# light_controller.net
KiCad netlist of a schematic drawn in EAGLE
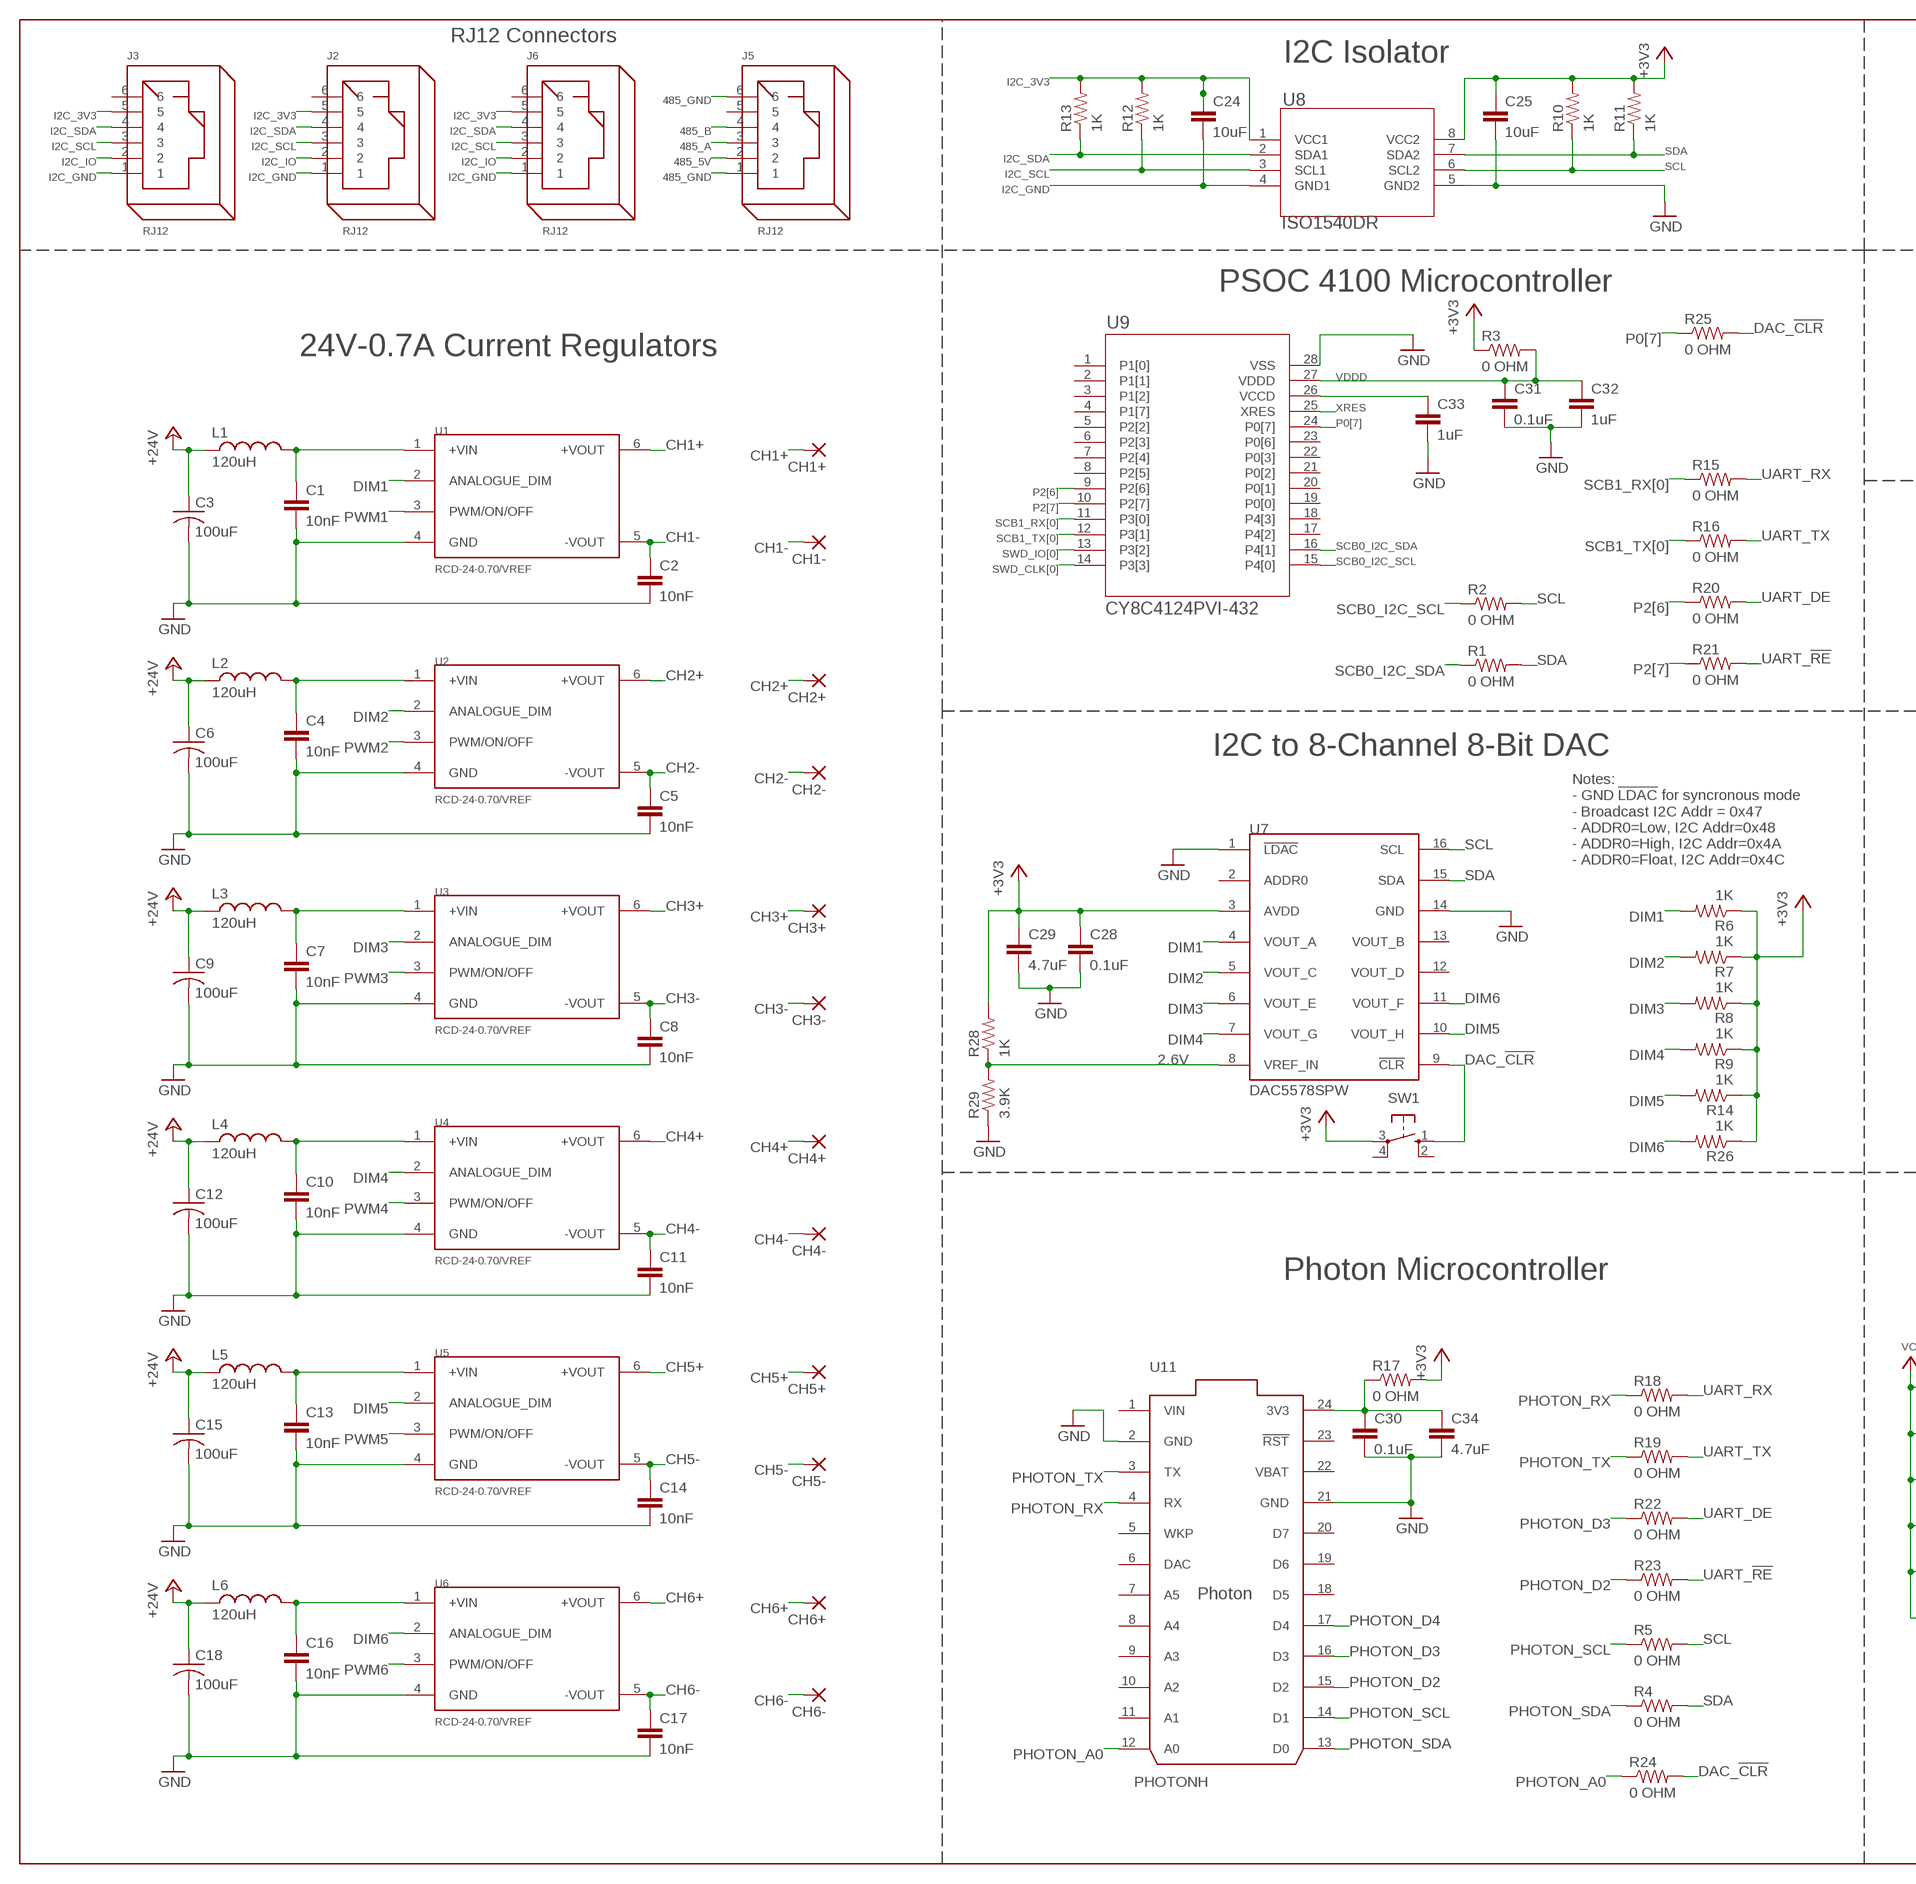
[diagram p0: schematic, sheet 1, part 1 of 2]
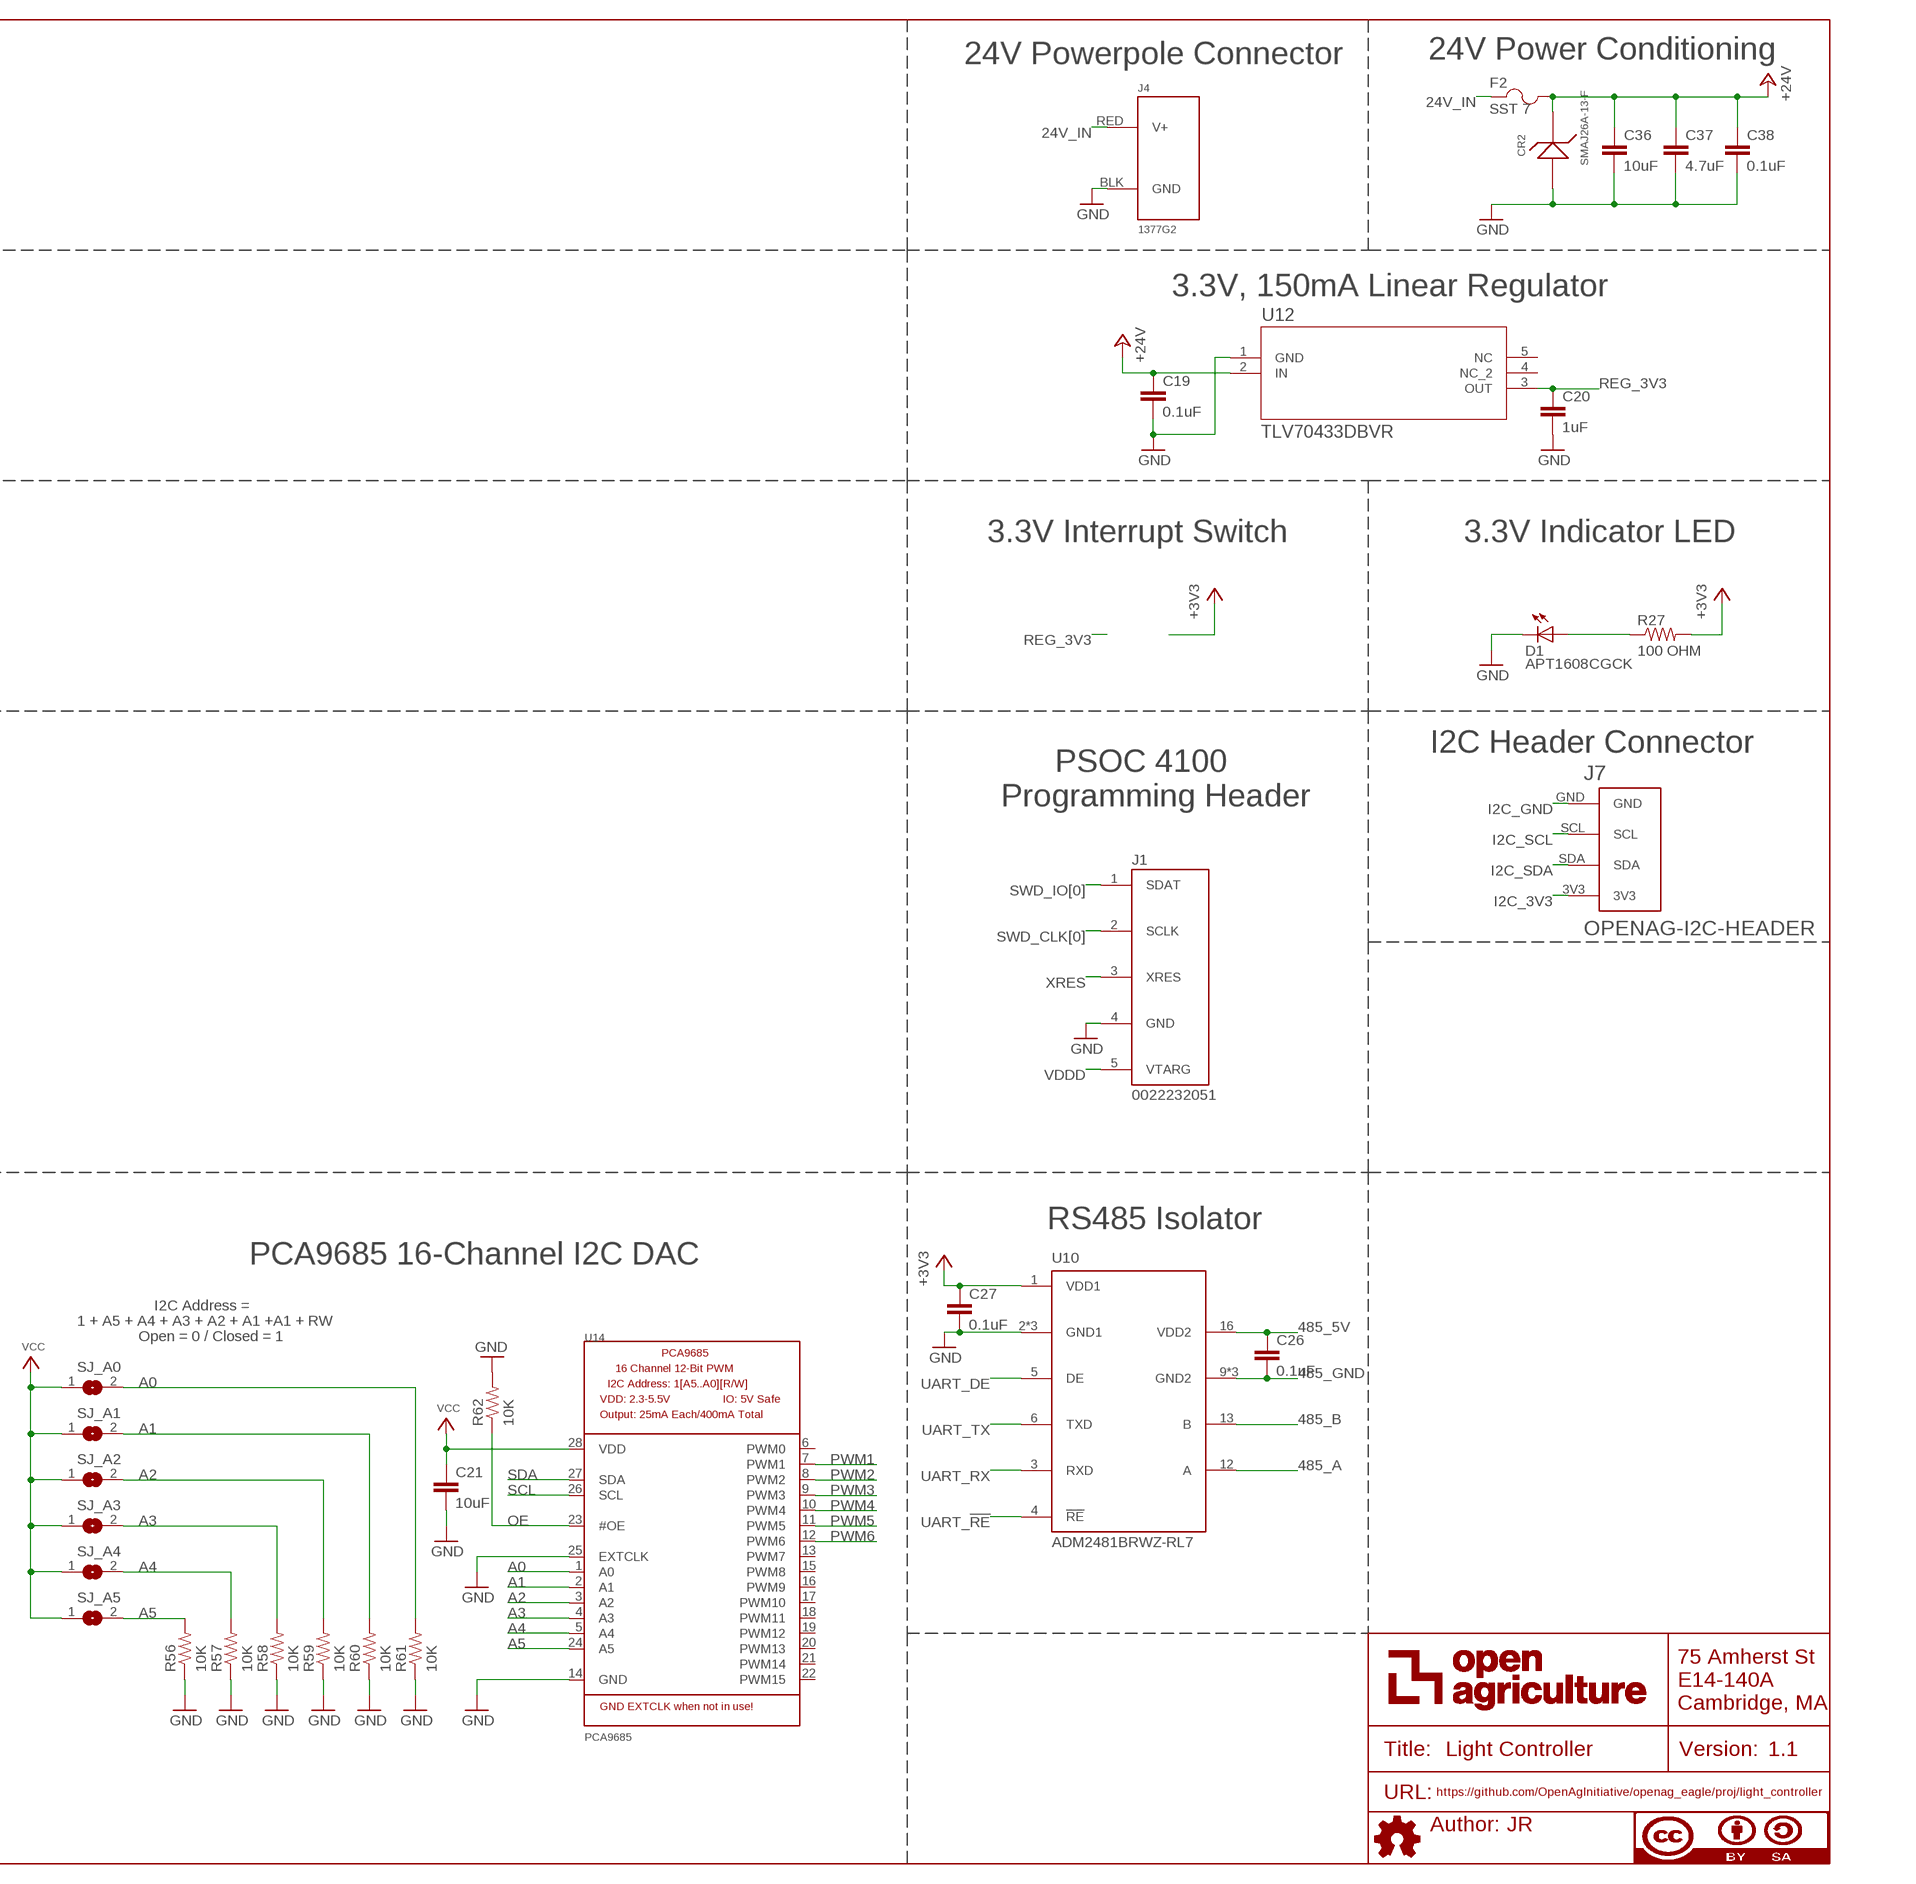
[diagram p1: schematic, sheet 1, part 2 of 2]

(export (version "E")
  (design (tool "Eeschema 10.0.6"))
  (components
    (comp (ref "C1")
      (value "10nF")
      (footprint "eagle-import:C0603")
      (libsource (lib "eagle-import") (part "10NF-C0603C103K5RACTU"))
    )
    (comp (ref "C2")
      (value "10nF")
      (footprint "eagle-import:C0603")
      (libsource (lib "eagle-import") (part "10NF-C0603C103K5RACTU"))
    )
    (comp (ref "C3")
      (value "100uF")
      (footprint "eagle-import:EEE-1HA101UP")
      (libsource (lib "eagle-import") (part "100UF-EEE-1HA101UP"))
    )
    (comp (ref "C4")
      (value "10nF")
      (footprint "eagle-import:C0603")
      (libsource (lib "eagle-import") (part "10NF-C0603C103K5RACTU"))
    )
    (comp (ref "C5")
      (value "10nF")
      (footprint "eagle-import:C0603")
      (libsource (lib "eagle-import") (part "10NF-C0603C103K5RACTU"))
    )
    (comp (ref "C6")
      (value "100uF")
      (footprint "eagle-import:EEE-1HA101UP")
      (libsource (lib "eagle-import") (part "100UF-EEE-1HA101UP"))
    )
    (comp (ref "C7")
      (value "10nF")
      (footprint "eagle-import:C0603")
      (libsource (lib "eagle-import") (part "10NF-C0603C103K5RACTU"))
    )
    (comp (ref "C8")
      (value "10nF")
      (footprint "eagle-import:C0603")
      (libsource (lib "eagle-import") (part "10NF-C0603C103K5RACTU"))
    )
    (comp (ref "C9")
      (value "100uF")
      (footprint "eagle-import:EEE-1HA101UP")
      (libsource (lib "eagle-import") (part "100UF-EEE-1HA101UP"))
    )
    (comp (ref "C10")
      (value "10nF")
      (footprint "eagle-import:C0603")
      (libsource (lib "eagle-import") (part "10NF-C0603C103K5RACTU"))
    )
    (comp (ref "C11")
      (value "10nF")
      (footprint "eagle-import:C0603")
      (libsource (lib "eagle-import") (part "10NF-C0603C103K5RACTU"))
    )
    (comp (ref "C12")
      (value "100uF")
      (footprint "eagle-import:EEE-1HA101UP")
      (libsource (lib "eagle-import") (part "100UF-EEE-1HA101UP"))
    )
    (comp (ref "C13")
      (value "10nF")
      (footprint "eagle-import:C0603")
      (libsource (lib "eagle-import") (part "10NF-C0603C103K5RACTU"))
    )
    (comp (ref "C14")
      (value "10nF")
      (footprint "eagle-import:C0603")
      (libsource (lib "eagle-import") (part "10NF-C0603C103K5RACTU"))
    )
    (comp (ref "C15")
      (value "100uF")
      (footprint "eagle-import:EEE-1HA101UP")
      (libsource (lib "eagle-import") (part "100UF-EEE-1HA101UP"))
    )
    (comp (ref "C16")
      (value "10nF")
      (footprint "eagle-import:C0603")
      (libsource (lib "eagle-import") (part "10NF-C0603C103K5RACTU"))
    )
    (comp (ref "C17")
      (value "10nF")
      (footprint "eagle-import:C0603")
      (libsource (lib "eagle-import") (part "10NF-C0603C103K5RACTU"))
    )
    (comp (ref "C18")
      (value "100uF")
      (footprint "eagle-import:EEE-1HA101UP")
      (libsource (lib "eagle-import") (part "100UF-EEE-1HA101UP"))
    )
    (comp (ref "C19")
      (value "0.1uF")
      (footprint "eagle-import:C0603")
      (libsource (lib "eagle-import") (part "0.1UF-C0603C104K5RACTU"))
    )
    (comp (ref "C20")
      (value "1uF")
      (footprint "eagle-import:C0603")
      (libsource (lib "eagle-import") (part "1UF-CL10A105KB8NNNC"))
    )
    (comp (ref "C21")
      (value "10uF")
      (footprint "eagle-import:C0805")
      (libsource (lib "eagle-import") (part "10UF-GMK212BBJ106KG-T"))
    )
    (comp (ref "C24")
      (value "10uF")
      (footprint "eagle-import:C0805")
      (libsource (lib "eagle-import") (part "10UF-GMK212BBJ106KG-T"))
    )
    (comp (ref "C25")
      (value "10uF")
      (footprint "eagle-import:C0805")
      (libsource (lib "eagle-import") (part "10UF-GMK212BBJ106KG-T"))
    )
    (comp (ref "C26")
      (value "0.1uF")
      (footprint "eagle-import:C0603")
      (libsource (lib "eagle-import") (part "0.1UF-C0603C104K5RACTU"))
    )
    (comp (ref "C27")
      (value "0.1uF")
      (footprint "eagle-import:C0603")
      (libsource (lib "eagle-import") (part "0.1UF-C0603C104K5RACTU"))
    )
    (comp (ref "C28")
      (value "0.1uF")
      (footprint "eagle-import:C0603")
      (libsource (lib "eagle-import") (part "0.1UF-C0603C104K5RACTU"))
    )
    (comp (ref "C29")
      (value "4.7uF")
      (footprint "eagle-import:C0805")
      (libsource (lib "eagle-import") (part "4.7UF-CL21A475KBQNNNE"))
    )
    (comp (ref "C30")
      (value "0.1uF")
      (footprint "eagle-import:C0603")
      (libsource (lib "eagle-import") (part "0.1UF-C0603C104K5RACTU"))
    )
    (comp (ref "C31")
      (value "0.1uF")
      (footprint "eagle-import:C0603")
      (libsource (lib "eagle-import") (part "0.1UF-C0603C104K5RACTU"))
    )
    (comp (ref "C32")
      (value "1uF")
      (footprint "eagle-import:C0603")
      (libsource (lib "eagle-import") (part "1UF-CL10A105KB8NNNC"))
    )
    (comp (ref "C33")
      (value "1uF")
      (footprint "eagle-import:C0603")
      (libsource (lib "eagle-import") (part "1UF-CL10A105KB8NNNC"))
    )
    (comp (ref "C34")
      (value "4.7uF")
      (footprint "eagle-import:C0805")
      (libsource (lib "eagle-import") (part "4.7UF-CL21A475KBQNNNE"))
    )
    (comp (ref "C36")
      (value "10uF")
      (footprint "eagle-import:C0805")
      (libsource (lib "eagle-import") (part "10UF-GMK212BBJ106KG-T"))
    )
    (comp (ref "C37")
      (value "4.7uF")
      (footprint "eagle-import:C0805")
      (libsource (lib "eagle-import") (part "4.7UF-CL21A475KBQNNNE"))
    )
    (comp (ref "C38")
      (value "0.1uF")
      (footprint "eagle-import:C0603")
      (libsource (lib "eagle-import") (part "0.1UF-C0603C104K5RACTU"))
    )
    (comp (ref "CH1+")
      (value "3,17/1,3")
      (footprint "eagle-import:3,17_1,3")
      (libsource (lib "eagle-import") (part "3,17/1,3"))
    )
    (comp (ref "CH1-")
      (value "3,17/1,3")
      (footprint "eagle-import:3,17_1,3")
      (libsource (lib "eagle-import") (part "3,17/1,3"))
    )
    (comp (ref "CH2+")
      (value "3,17/1,3")
      (footprint "eagle-import:3,17_1,3")
      (libsource (lib "eagle-import") (part "3,17/1,3"))
    )
    (comp (ref "CH2-")
      (value "3,17/1,3")
      (footprint "eagle-import:3,17_1,3")
      (libsource (lib "eagle-import") (part "3,17/1,3"))
    )
    (comp (ref "CH3+")
      (value "3,17/1,3")
      (footprint "eagle-import:3,17_1,3")
      (libsource (lib "eagle-import") (part "3,17/1,3"))
    )
    (comp (ref "CH3-")
      (value "3,17/1,3")
      (footprint "eagle-import:3,17_1,3")
      (libsource (lib "eagle-import") (part "3,17/1,3"))
    )
    (comp (ref "CH4+")
      (value "3,17/1,3")
      (footprint "eagle-import:3,17_1,3")
      (libsource (lib "eagle-import") (part "3,17/1,3"))
    )
    (comp (ref "CH4-")
      (value "3,17/1,3")
      (footprint "eagle-import:3,17_1,3")
      (libsource (lib "eagle-import") (part "3,17/1,3"))
    )
    (comp (ref "CH5+")
      (value "3,17/1,3")
      (footprint "eagle-import:3,17_1,3")
      (libsource (lib "eagle-import") (part "3,17/1,3"))
    )
    (comp (ref "CH5-")
      (value "3,17/1,3")
      (footprint "eagle-import:3,17_1,3")
      (libsource (lib "eagle-import") (part "3,17/1,3"))
    )
    (comp (ref "CH6+")
      (value "3,17/1,3")
      (footprint "eagle-import:3,17_1,3")
      (libsource (lib "eagle-import") (part "3,17/1,3"))
    )
    (comp (ref "CH6-")
      (value "3,17/1,3")
      (footprint "eagle-import:3,17_1,3")
      (libsource (lib "eagle-import") (part "3,17/1,3"))
    )
    (comp (ref "CR2")
      (value "SMAJ26A-13-F")
      (footprint "eagle-import:SMA")
      (libsource (lib "eagle-import") (part "SMAJ26A-13-F"))
    )
    (comp (ref "D1")
      (value "APT1608CGCK")
      (footprint "eagle-import:CHIPLED_0603")
      (libsource (lib "eagle-import") (part "APT1608CGCK"))
    )
    (comp (ref "F2")
      (value "SST 7")
      (footprint "eagle-import:SS")
      (libsource (lib "eagle-import") (part "SST_7"))
    )
    (comp (ref "FRAME1")
      (value "DOCFIELD")
      (footprint "eagle-import:DOCFIELD")
      (fields
        (field (name "TITLE") "Example Template")
        (field (name "AUTHOR") "XX")
        (field (name "VER") "1.0")
        (field (name "URL") "https://github.com/OpenAgInitiative/openag_eagle_template")
        (field (name "AUTHOR_1") "JR")
        (field (name "TITLE_1") "Light Controller")
        (field (name "URL_1") "https://github.com/OpenAgInitiative/openag_eagle/proj/light_controller")
        (field (name "VER_1") "1.1")
      )
      (libsource (lib "eagle-import") (part "DOCFIELD"))
    )
    (comp (ref "J1")
      (value "0022232051")
      (footprint "eagle-import:22-23-2051")
      (libsource (lib "eagle-import") (part "MINI-PROG3-5POS-MATING-CONNECTOR"))
    )
    (comp (ref "J2")
      (value "RJ12")
      (footprint "eagle-import:RJ12")
      (libsource (lib "eagle-import") (part "A-2004-1-4-LP-N-R"))
    )
    (comp (ref "J3")
      (value "RJ12")
      (footprint "eagle-import:RJ12")
      (libsource (lib "eagle-import") (part "A-2004-1-4-LP-N-R"))
    )
    (comp (ref "J4")
      (value "1377G2")
      (footprint "eagle-import:1377G2")
      (libsource (lib "eagle-import") (part "1377G21377G2"))
    )
    (comp (ref "J5")
      (value "RJ12")
      (footprint "eagle-import:RJ12")
      (libsource (lib "eagle-import") (part "A-2004-1-4-LP-N-R"))
    )
    (comp (ref "J6")
      (value "RJ12")
      (footprint "eagle-import:RJ12")
      (libsource (lib "eagle-import") (part "A-2004-1-4-LP-N-R"))
    )
    (comp (ref "J7")
      (value "OPENAG-I2C-HEADER")
      (footprint "eagle-import:OPENAG-I2C-HEADER")
      (libsource (lib "eagle-import") (part "OPENAG-I2C-HEADER"))
    )
    (comp (ref "L1")
      (value "120uH")
      (footprint "eagle-import:74404064121")
      (libsource (lib "eagle-import") (part "120UH-74404064121"))
    )
    (comp (ref "L2")
      (value "120uH")
      (footprint "eagle-import:74404064121")
      (libsource (lib "eagle-import") (part "120UH-74404064121"))
    )
    (comp (ref "L3")
      (value "120uH")
      (footprint "eagle-import:74404064121")
      (libsource (lib "eagle-import") (part "120UH-74404064121"))
    )
    (comp (ref "L4")
      (value "120uH")
      (footprint "eagle-import:74404064121")
      (libsource (lib "eagle-import") (part "120UH-74404064121"))
    )
    (comp (ref "L5")
      (value "120uH")
      (footprint "eagle-import:74404064121")
      (libsource (lib "eagle-import") (part "120UH-74404064121"))
    )
    (comp (ref "L6")
      (value "120uH")
      (footprint "eagle-import:74404064121")
      (libsource (lib "eagle-import") (part "120UH-74404064121"))
    )
    (comp (ref "R1")
      (value "0 OHM")
      (footprint "eagle-import:RC0603N")
      (libsource (lib "eagle-import") (part "0OHM-RC0603JR-070RL"))
    )
    (comp (ref "R2")
      (value "0 OHM")
      (footprint "eagle-import:RC0603N")
      (libsource (lib "eagle-import") (part "0OHM-RC0603JR-070RL"))
    )
    (comp (ref "R3")
      (value "0 OHM")
      (footprint "eagle-import:RC0603N")
      (libsource (lib "eagle-import") (part "0OHM-RC0603JR-070RL"))
    )
    (comp (ref "R4")
      (value "0 OHM")
      (footprint "eagle-import:RC0603N")
      (libsource (lib "eagle-import") (part "0OHM-RC0603JR-070RL"))
    )
    (comp (ref "R5")
      (value "0 OHM")
      (footprint "eagle-import:RC0603N")
      (libsource (lib "eagle-import") (part "0OHM-RC0603JR-070RL"))
    )
    (comp (ref "R6")
      (value "1K")
      (footprint "eagle-import:RC0603N")
      (libsource (lib "eagle-import") (part "1K-ERJ-PB3D1001V"))
    )
    (comp (ref "R7")
      (value "1K")
      (footprint "eagle-import:RC0603N")
      (libsource (lib "eagle-import") (part "1K-ERJ-PB3D1001V"))
    )
    (comp (ref "R8")
      (value "1K")
      (footprint "eagle-import:RC0603N")
      (libsource (lib "eagle-import") (part "1K-ERJ-PB3D1001V"))
    )
    (comp (ref "R9")
      (value "1K")
      (footprint "eagle-import:RC0603N")
      (libsource (lib "eagle-import") (part "1K-ERJ-PB3D1001V"))
    )
    (comp (ref "R10")
      (value "1K")
      (footprint "eagle-import:RC0603N")
      (libsource (lib "eagle-import") (part "1K-ERJ-PB3D1001V"))
    )
    (comp (ref "R11")
      (value "1K")
      (footprint "eagle-import:RC0603N")
      (libsource (lib "eagle-import") (part "1K-ERJ-PB3D1001V"))
    )
    (comp (ref "R12")
      (value "1K")
      (footprint "eagle-import:RC0603N")
      (libsource (lib "eagle-import") (part "1K-ERJ-PB3D1001V"))
    )
    (comp (ref "R13")
      (value "1K")
      (footprint "eagle-import:RC0603N")
      (libsource (lib "eagle-import") (part "1K-ERJ-PB3D1001V"))
    )
    (comp (ref "R14")
      (value "1K")
      (footprint "eagle-import:RC0603N")
      (libsource (lib "eagle-import") (part "1K-ERJ-PB3D1001V"))
    )
    (comp (ref "R15")
      (value "0 OHM")
      (footprint "eagle-import:RC0603N")
      (libsource (lib "eagle-import") (part "0OHM-RC0603JR-070RL"))
    )
    (comp (ref "R16")
      (value "0 OHM")
      (footprint "eagle-import:RC0603N")
      (libsource (lib "eagle-import") (part "0OHM-RC0603JR-070RL"))
    )
    (comp (ref "R17")
      (value "0 OHM")
      (footprint "eagle-import:RC0603N")
      (libsource (lib "eagle-import") (part "0OHM-RC0603JR-070RL"))
    )
    (comp (ref "R18")
      (value "0 OHM")
      (footprint "eagle-import:RC0603N")
      (libsource (lib "eagle-import") (part "0OHM-RC0603JR-070RL"))
    )
    (comp (ref "R19")
      (value "0 OHM")
      (footprint "eagle-import:RC0603N")
      (libsource (lib "eagle-import") (part "0OHM-RC0603JR-070RL"))
    )
    (comp (ref "R20")
      (value "0 OHM")
      (footprint "eagle-import:RC0603N")
      (libsource (lib "eagle-import") (part "0OHM-RC0603JR-070RL"))
    )
    (comp (ref "R21")
      (value "0 OHM")
      (footprint "eagle-import:RC0603N")
      (libsource (lib "eagle-import") (part "0OHM-RC0603JR-070RL"))
    )
    (comp (ref "R22")
      (value "0 OHM")
      (footprint "eagle-import:RC0603N")
      (libsource (lib "eagle-import") (part "0OHM-RC0603JR-070RL"))
    )
    (comp (ref "R23")
      (value "0 OHM")
      (footprint "eagle-import:RC0603N")
      (libsource (lib "eagle-import") (part "0OHM-RC0603JR-070RL"))
    )
    (comp (ref "R24")
      (value "0 OHM")
      (footprint "eagle-import:RC0603N")
      (libsource (lib "eagle-import") (part "0OHM-RC0603JR-070RL"))
    )
    (comp (ref "R25")
      (value "0 OHM")
      (footprint "eagle-import:RC0603N")
      (libsource (lib "eagle-import") (part "0OHM-RC0603JR-070RL"))
    )
    (comp (ref "R26")
      (value "1K")
      (footprint "eagle-import:RC0603N")
      (libsource (lib "eagle-import") (part "1K-ERJ-PB3D1001V"))
    )
    (comp (ref "R27")
      (value "100 OHM")
      (footprint "eagle-import:RC0603N")
      (libsource (lib "eagle-import") (part "100OHM-RC0603JR-07100RL"))
    )
    (comp (ref "R28")
      (value "1K")
      (footprint "eagle-import:RC0603N")
      (libsource (lib "eagle-import") (part "1K-ERJ-PB3D1001V"))
    )
    (comp (ref "R29")
      (value "3.9K")
      (footprint "eagle-import:RC0603N")
      (libsource (lib "eagle-import") (part "3.9K-RC0603JR-073K9L"))
    )
    (comp (ref "R56")
      (value "10K")
      (footprint "eagle-import:RC0603N")
      (libsource (lib "eagle-import") (part "10K-ERJ-3EKF1002V"))
    )
    (comp (ref "R57")
      (value "10K")
      (footprint "eagle-import:RC0603N")
      (libsource (lib "eagle-import") (part "10K-ERJ-3EKF1002V"))
    )
    (comp (ref "R58")
      (value "10K")
      (footprint "eagle-import:RC0603N")
      (libsource (lib "eagle-import") (part "10K-ERJ-3EKF1002V"))
    )
    (comp (ref "R59")
      (value "10K")
      (footprint "eagle-import:RC0603N")
      (libsource (lib "eagle-import") (part "10K-ERJ-3EKF1002V"))
    )
    (comp (ref "R60")
      (value "10K")
      (footprint "eagle-import:RC0603N")
      (libsource (lib "eagle-import") (part "10K-ERJ-3EKF1002V"))
    )
    (comp (ref "R61")
      (value "10K")
      (footprint "eagle-import:RC0603N")
      (libsource (lib "eagle-import") (part "10K-ERJ-3EKF1002V"))
    )
    (comp (ref "R62")
      (value "10K")
      (footprint "eagle-import:RC0603N")
      (libsource (lib "eagle-import") (part "10K-ERJ-3EKF1002V"))
    )
    (comp (ref "SJ_A0")
      (value "SOLDERJUMPERREFLOW_NOPASTE")
      (footprint "eagle-import:SOLDERJUMPER_REFLOW_NOPASTE")
      (libsource (lib "eagle-import") (part "SOLDERJUMPERREFLOW_NOPASTE"))
    )
    (comp (ref "SJ_A1")
      (value "SOLDERJUMPERREFLOW_NOPASTE")
      (footprint "eagle-import:SOLDERJUMPER_REFLOW_NOPASTE")
      (libsource (lib "eagle-import") (part "SOLDERJUMPERREFLOW_NOPASTE"))
    )
    (comp (ref "SJ_A2")
      (value "SOLDERJUMPERREFLOW_NOPASTE")
      (footprint "eagle-import:SOLDERJUMPER_REFLOW_NOPASTE")
      (libsource (lib "eagle-import") (part "SOLDERJUMPERREFLOW_NOPASTE"))
    )
    (comp (ref "SJ_A3")
      (value "SOLDERJUMPERREFLOW_NOPASTE")
      (footprint "eagle-import:SOLDERJUMPER_REFLOW_NOPASTE")
      (libsource (lib "eagle-import") (part "SOLDERJUMPERREFLOW_NOPASTE"))
    )
    (comp (ref "SJ_A4")
      (value "SOLDERJUMPERREFLOW_NOPASTE")
      (footprint "eagle-import:SOLDERJUMPER_REFLOW_NOPASTE")
      (libsource (lib "eagle-import") (part "SOLDERJUMPERREFLOW_NOPASTE"))
    )
    (comp (ref "SJ_A5")
      (value "SOLDERJUMPERREFLOW_NOPASTE")
      (footprint "eagle-import:SOLDERJUMPER_REFLOW_NOPASTE")
      (libsource (lib "eagle-import") (part "SOLDERJUMPERREFLOW_NOPASTE"))
    )
    (comp (ref "SW1")
      (value "BF3-1020")
      (footprint "eagle-import:B3F-10XX")
      (libsource (lib "eagle-import") (part "BF3-1020"))
    )
    (comp (ref "U1")
      (value "RCD-24-0.70/VREF")
      (footprint "eagle-import:RCD-24-PINNED")
      (libsource (lib "eagle-import") (part "RCD-24-0.70/VREF"))
    )
    (comp (ref "U2")
      (value "RCD-24-0.70/VREF")
      (footprint "eagle-import:RCD-24-PINNED")
      (libsource (lib "eagle-import") (part "RCD-24-0.70/VREF"))
    )
    (comp (ref "U3")
      (value "RCD-24-0.70/VREF")
      (footprint "eagle-import:RCD-24-PINNED")
      (libsource (lib "eagle-import") (part "RCD-24-0.70/VREF"))
    )
    (comp (ref "U4")
      (value "RCD-24-0.70/VREF")
      (footprint "eagle-import:RCD-24-PINNED")
      (libsource (lib "eagle-import") (part "RCD-24-0.70/VREF"))
    )
    (comp (ref "U5")
      (value "RCD-24-0.70/VREF")
      (footprint "eagle-import:RCD-24-PINNED")
      (libsource (lib "eagle-import") (part "RCD-24-0.70/VREF"))
    )
    (comp (ref "U6")
      (value "RCD-24-0.70/VREF")
      (footprint "eagle-import:RCD-24-PINNED")
      (libsource (lib "eagle-import") (part "RCD-24-0.70/VREF"))
    )
    (comp (ref "U7")
      (value "DAC5578SPW")
      (footprint "eagle-import:TSSOP16")
      (libsource (lib "eagle-import") (part "DAC5578SPW"))
    )
    (comp (ref "U8")
      (value "ISO1540DR")
      (footprint "eagle-import:D8")
      (libsource (lib "eagle-import") (part "ISO1540DR"))
    )
    (comp (ref "U9")
      (value "CY8C4124PVI-432")
      (footprint "eagle-import:SSOP-28")
      (libsource (lib "eagle-import") (part "CY8C4124PVI-432"))
    )
    (comp (ref "U10")
      (value "ADM2481BRWZ-RL7")
      (footprint "eagle-import:SOIC16LWB")
      (libsource (lib "eagle-import") (part "ADM2481BRWZ-RL7"))
    )
    (comp (ref "U11")
      (value "PHOTONH")
      (footprint "eagle-import:PHOTON")
      (libsource (lib "eagle-import") (part "PHOTONHPHOTONH"))
    )
    (comp (ref "U12")
      (value "TLV70433DBVR")
      (footprint "eagle-import:DBV5-M")
      (libsource (lib "eagle-import") (part "TLV70433DBVRDBV5-M"))
    )
    (comp (ref "U14")
      (value "PCA9685")
      (footprint "eagle-import:TSSOP28")
      (libsource (lib "eagle-import") (part "PCA9685PW/Q900,118"))
    )
  )
  (nets
    (net (code "1") (name "+3V3") (class "Default")
      (node (ref "C25") (pin "1") (pinfunction "1_1") (pintype "passive"))
      (node (ref "C27") (pin "1") (pinfunction "1_1") (pintype "passive"))
      (node (ref "C28") (pin "1") (pinfunction "1_1") (pintype "passive"))
      (node (ref "C29") (pin "1") (pinfunction "1_1") (pintype "passive"))
      (node (ref "R10") (pin "2") (pinfunction "2_2") (pintype "passive"))
      (node (ref "R11") (pin "2") (pinfunction "2_2") (pintype "passive"))
      (node (ref "R14") (pin "1") (pinfunction "1_1") (pintype "passive"))
      (node (ref "R17") (pin "2") (pinfunction "2_2") (pintype "passive"))
      (node (ref "R26") (pin "1") (pinfunction "1_1") (pintype "passive"))
      (node (ref "R27") (pin "2") (pinfunction "2_2") (pintype "passive"))
      (node (ref "R28") (pin "2") (pinfunction "2_2") (pintype "passive"))
      (node (ref "R3") (pin "1") (pinfunction "1_1") (pintype "passive"))
      (node (ref "R6") (pin "1") (pinfunction "1_1") (pintype "passive"))
      (node (ref "R7") (pin "1") (pinfunction "1_1") (pintype "passive"))
      (node (ref "R8") (pin "1") (pinfunction "1_1") (pintype "passive"))
      (node (ref "R9") (pin "1") (pinfunction "1_1") (pintype "passive"))
      (node (ref "SW1") (pin "3") (pinfunction "P_3") (pintype "passive"))
      (node (ref "U10") (pin "1") (pinfunction "VDD1_1") (pintype "bidirectional"))
      (node (ref "U7") (pin "3") (pinfunction "AVDD_3") (pintype "bidirectional"))
      (node (ref "U8") (pin "8") (pinfunction "VCC2_8") (pintype "power_in"))
    )
    (net (code "2") (name "+24V") (class "Default")
      (node (ref "C12") (pin "+") (pinfunction "1(+)_+") (pintype "passive"))
      (node (ref "C15") (pin "+") (pinfunction "1(+)_+") (pintype "passive"))
      (node (ref "C18") (pin "+") (pinfunction "1(+)_+") (pintype "passive"))
      (node (ref "C19") (pin "1") (pinfunction "1_1") (pintype "passive"))
      (node (ref "C3") (pin "+") (pinfunction "1(+)_+") (pintype "passive"))
      (node (ref "C36") (pin "1") (pinfunction "1_1") (pintype "passive"))
      (node (ref "C37") (pin "1") (pinfunction "1_1") (pintype "passive"))
      (node (ref "C38") (pin "1") (pinfunction "1_1") (pintype "passive"))
      (node (ref "C6") (pin "+") (pinfunction "1(+)_+") (pintype "passive"))
      (node (ref "C9") (pin "+") (pinfunction "1(+)_+") (pintype "passive"))
      (node (ref "CR2") (pin "1") (pinfunction "P$2_1") (pintype "bidirectional"))
      (node (ref "F2") (pin "2") (pinfunction "2_2") (pintype "passive"))
      (node (ref "L1") (pin "1") (pinfunction "1_1") (pintype "passive"))
      (node (ref "L2") (pin "1") (pinfunction "1_1") (pintype "passive"))
      (node (ref "L3") (pin "1") (pinfunction "1_1") (pintype "passive"))
      (node (ref "L4") (pin "1") (pinfunction "1_1") (pintype "passive"))
      (node (ref "L5") (pin "1") (pinfunction "1_1") (pintype "passive"))
      (node (ref "L6") (pin "1") (pinfunction "1_1") (pintype "passive"))
      (node (ref "U12") (pin "2") (pinfunction "IN_2") (pintype "input"))
    )
    (net (code "3") (name "/2.6V") (class "Default")
      (node (ref "R28") (pin "1") (pinfunction "1_1") (pintype "passive"))
      (node (ref "R29") (pin "2") (pinfunction "2_2") (pintype "passive"))
      (node (ref "U7") (pin "8") (pinfunction "VREF_IN_8") (pintype "bidirectional"))
    )
    (net (code "4") (name "/A0") (class "Default")
      (node (ref "R61") (pin "2") (pinfunction "2_2") (pintype "passive"))
      (node (ref "SJ_A0") (pin "2") (pinfunction "2_2") (pintype "passive"))
      (node (ref "U14") (pin "1") (pinfunction "A0_1") (pintype "bidirectional"))
    )
    (net (code "5") (name "/A1") (class "Default")
      (node (ref "R60") (pin "2") (pinfunction "2_2") (pintype "passive"))
      (node (ref "SJ_A1") (pin "2") (pinfunction "2_2") (pintype "passive"))
      (node (ref "U14") (pin "2") (pinfunction "A1_2") (pintype "bidirectional"))
    )
    (net (code "6") (name "/A2") (class "Default")
      (node (ref "R59") (pin "2") (pinfunction "2_2") (pintype "passive"))
      (node (ref "SJ_A2") (pin "2") (pinfunction "2_2") (pintype "passive"))
      (node (ref "U14") (pin "3") (pinfunction "A2_3") (pintype "bidirectional"))
    )
    (net (code "7") (name "/A3") (class "Default")
      (node (ref "R58") (pin "2") (pinfunction "2_2") (pintype "passive"))
      (node (ref "SJ_A3") (pin "2") (pinfunction "2_2") (pintype "passive"))
      (node (ref "U14") (pin "4") (pinfunction "A3_4") (pintype "bidirectional"))
    )
    (net (code "8") (name "/A4") (class "Default")
      (node (ref "R57") (pin "2") (pinfunction "2_2") (pintype "passive"))
      (node (ref "SJ_A4") (pin "2") (pinfunction "2_2") (pintype "passive"))
      (node (ref "U14") (pin "5") (pinfunction "A4_5") (pintype "bidirectional"))
    )
    (net (code "9") (name "/A5") (class "Default")
      (node (ref "R56") (pin "2") (pinfunction "2_2") (pintype "passive"))
      (node (ref "SJ_A5") (pin "2") (pinfunction "2_2") (pintype "passive"))
      (node (ref "U14") (pin "24") (pinfunction "A5_24") (pintype "bidirectional"))
    )
    (net (code "10") (name "/DAC_~{CLR}") (class "Default")
      (node (ref "R24") (pin "2") (pinfunction "2_2") (pintype "passive"))
      (node (ref "R25") (pin "2") (pinfunction "2_2") (pintype "passive"))
      (node (ref "SW1") (pin "1") (pinfunction "S_1") (pintype "passive"))
      (node (ref "U7") (pin "9") (pinfunction "~{CLR}_9") (pintype "bidirectional"))
    )
    (net (code "11") (name "/OE") (class "Default")
      (node (ref "R62") (pin "1") (pinfunction "1_1") (pintype "passive"))
      (node (ref "U14") (pin "23") (pinfunction "#OE_23") (pintype "input"))
    )
    (net (code "12") (name "/UART_~{RE}") (class "Default")
      (node (ref "R21") (pin "2") (pinfunction "2_2") (pintype "passive"))
      (node (ref "R23") (pin "2") (pinfunction "2_2") (pintype "passive"))
      (node (ref "U10") (pin "4") (pinfunction "~{RE}_4") (pintype "bidirectional"))
    )
    (net (code "13") (name "/VBAT") (class "Default")
      (node (ref "U11") (pin "22") (pinfunction "VBAT_22") (pintype "power_in"))
    )
    (net (code "14") (name "/VIN") (class "Default")
      (node (ref "U11") (pin "1") (pinfunction "VIN_1") (pintype "power_in"))
    )
    (net (code "15") (name "24V_IN") (class "Default")
      (node (ref "F2") (pin "1") (pinfunction "1_1") (pintype "passive"))
      (node (ref "J4") (pin "RED") (pinfunction "V+_RED") (pintype "power_in"))
    )
    (net (code "16") (name "485_5V") (class "Default")
      (node (ref "C26") (pin "1") (pinfunction "1_1") (pintype "passive"))
      (node (ref "J5") (pin "2") (pinfunction "2_2") (pintype "bidirectional"))
      (node (ref "U10") (pin "16") (pinfunction "VDD2_16") (pintype "bidirectional"))
    )
    (net (code "17") (name "485_A") (class "Default")
      (node (ref "J5") (pin "3") (pinfunction "3_3") (pintype "bidirectional"))
      (node (ref "U10") (pin "12") (pinfunction "A_12") (pintype "bidirectional"))
    )
    (net (code "18") (name "485_B") (class "Default")
      (node (ref "J5") (pin "4") (pinfunction "4_4") (pintype "bidirectional"))
      (node (ref "U10") (pin "13") (pinfunction "B_13") (pintype "bidirectional"))
    )
    (net (code "19") (name "485_GND") (class "Default")
      (node (ref "C26") (pin "2") (pinfunction "2_2") (pintype "passive"))
      (node (ref "J5") (pin "1") (pinfunction "1_1") (pintype "bidirectional"))
      (node (ref "J5") (pin "6") (pinfunction "6_6") (pintype "bidirectional"))
      (node (ref "U10") (pin "10") (pinfunction "GND2_10") (pintype "bidirectional"))
      (node (ref "U10") (pin "15") (pinfunction "GND2_15") (pintype "bidirectional"))
      (node (ref "U10") (pin "9") (pinfunction "GND2_9") (pintype "bidirectional"))
    )
    (net (code "20") (name "CH1+") (class "Default")
      (node (ref "CH1+") (pin "1") (pinfunction "P_1") (pintype "passive"))
      (node (ref "U1") (pin "6") (pinfunction "+VOUT_6") (pintype "power_in"))
    )
    (net (code "21") (name "CH1-") (class "Default")
      (node (ref "C2") (pin "1") (pinfunction "1_1") (pintype "passive"))
      (node (ref "CH1-") (pin "1") (pinfunction "P_1") (pintype "passive"))
      (node (ref "U1") (pin "5") (pinfunction "-VOUT_5") (pintype "power_in"))
    )
    (net (code "22") (name "CH2+") (class "Default")
      (node (ref "CH2+") (pin "1") (pinfunction "P_1") (pintype "passive"))
      (node (ref "U2") (pin "6") (pinfunction "+VOUT_6") (pintype "power_in"))
    )
    (net (code "23") (name "CH2-") (class "Default")
      (node (ref "C5") (pin "1") (pinfunction "1_1") (pintype "passive"))
      (node (ref "CH2-") (pin "1") (pinfunction "P_1") (pintype "passive"))
      (node (ref "U2") (pin "5") (pinfunction "-VOUT_5") (pintype "power_in"))
    )
    (net (code "24") (name "CH3+") (class "Default")
      (node (ref "CH3+") (pin "1") (pinfunction "P_1") (pintype "passive"))
      (node (ref "U3") (pin "6") (pinfunction "+VOUT_6") (pintype "power_in"))
    )
    (net (code "25") (name "CH3-") (class "Default")
      (node (ref "C8") (pin "1") (pinfunction "1_1") (pintype "passive"))
      (node (ref "CH3-") (pin "1") (pinfunction "P_1") (pintype "passive"))
      (node (ref "U3") (pin "5") (pinfunction "-VOUT_5") (pintype "power_in"))
    )
    (net (code "26") (name "CH4+") (class "Default")
      (node (ref "CH4+") (pin "1") (pinfunction "P_1") (pintype "passive"))
      (node (ref "U4") (pin "6") (pinfunction "+VOUT_6") (pintype "power_in"))
    )
    (net (code "27") (name "CH4-") (class "Default")
      (node (ref "C11") (pin "1") (pinfunction "1_1") (pintype "passive"))
      (node (ref "CH4-") (pin "1") (pinfunction "P_1") (pintype "passive"))
      (node (ref "U4") (pin "5") (pinfunction "-VOUT_5") (pintype "power_in"))
    )
    (net (code "28") (name "CH5+") (class "Default")
      (node (ref "CH5+") (pin "1") (pinfunction "P_1") (pintype "passive"))
      (node (ref "U5") (pin "6") (pinfunction "+VOUT_6") (pintype "power_in"))
    )
    (net (code "29") (name "CH5-") (class "Default")
      (node (ref "C14") (pin "1") (pinfunction "1_1") (pintype "passive"))
      (node (ref "CH5-") (pin "1") (pinfunction "P_1") (pintype "passive"))
      (node (ref "U5") (pin "5") (pinfunction "-VOUT_5") (pintype "power_in"))
    )
    (net (code "30") (name "CH6+") (class "Default")
      (node (ref "CH6+") (pin "1") (pinfunction "P_1") (pintype "passive"))
      (node (ref "U6") (pin "6") (pinfunction "+VOUT_6") (pintype "power_in"))
    )
    (net (code "31") (name "CH6-") (class "Default")
      (node (ref "C17") (pin "1") (pinfunction "1_1") (pintype "passive"))
      (node (ref "CH6-") (pin "1") (pinfunction "P_1") (pintype "passive"))
      (node (ref "U6") (pin "5") (pinfunction "-VOUT_5") (pintype "power_in"))
    )
    (net (code "32") (name "DIM1") (class "Default")
      (node (ref "R6") (pin "2") (pinfunction "2_2") (pintype "passive"))
      (node (ref "U1") (pin "2") (pinfunction "ANALOGUE_DIM_2") (pintype "bidirectional"))
      (node (ref "U7") (pin "4") (pinfunction "VOUT_A_4") (pintype "bidirectional"))
    )
    (net (code "33") (name "DIM2") (class "Default")
      (node (ref "R7") (pin "2") (pinfunction "2_2") (pintype "passive"))
      (node (ref "U2") (pin "2") (pinfunction "ANALOGUE_DIM_2") (pintype "bidirectional"))
      (node (ref "U7") (pin "5") (pinfunction "VOUT_C_5") (pintype "bidirectional"))
    )
    (net (code "34") (name "DIM3") (class "Default")
      (node (ref "R8") (pin "2") (pinfunction "2_2") (pintype "passive"))
      (node (ref "U3") (pin "2") (pinfunction "ANALOGUE_DIM_2") (pintype "bidirectional"))
      (node (ref "U7") (pin "6") (pinfunction "VOUT_E_6") (pintype "bidirectional"))
    )
    (net (code "35") (name "DIM4") (class "Default")
      (node (ref "R9") (pin "2") (pinfunction "2_2") (pintype "passive"))
      (node (ref "U4") (pin "2") (pinfunction "ANALOGUE_DIM_2") (pintype "bidirectional"))
      (node (ref "U7") (pin "7") (pinfunction "VOUT_G_7") (pintype "bidirectional"))
    )
    (net (code "36") (name "DIM5") (class "Default")
      (node (ref "R14") (pin "2") (pinfunction "2_2") (pintype "passive"))
      (node (ref "U5") (pin "2") (pinfunction "ANALOGUE_DIM_2") (pintype "bidirectional"))
      (node (ref "U7") (pin "10") (pinfunction "VOUT_H_10") (pintype "bidirectional"))
    )
    (net (code "37") (name "DIM6") (class "Default")
      (node (ref "R26") (pin "2") (pinfunction "2_2") (pintype "passive"))
      (node (ref "U6") (pin "2") (pinfunction "ANALOGUE_DIM_2") (pintype "bidirectional"))
      (node (ref "U7") (pin "11") (pinfunction "VOUT_F_11") (pintype "bidirectional"))
    )
    (net (code "38") (name "GND") (class "Default")
      (node (ref "C1") (pin "2") (pinfunction "2_2") (pintype "passive"))
      (node (ref "C10") (pin "2") (pinfunction "2_2") (pintype "passive"))
      (node (ref "C11") (pin "2") (pinfunction "2_2") (pintype "passive"))
      (node (ref "C12") (pin "-") (pinfunction "2(-)_-") (pintype "passive"))
      (node (ref "C13") (pin "2") (pinfunction "2_2") (pintype "passive"))
      (node (ref "C14") (pin "2") (pinfunction "2_2") (pintype "passive"))
      (node (ref "C15") (pin "-") (pinfunction "2(-)_-") (pintype "passive"))
      (node (ref "C16") (pin "2") (pinfunction "2_2") (pintype "passive"))
      (node (ref "C17") (pin "2") (pinfunction "2_2") (pintype "passive"))
      (node (ref "C18") (pin "-") (pinfunction "2(-)_-") (pintype "passive"))
      (node (ref "C19") (pin "2") (pinfunction "2_2") (pintype "passive"))
      (node (ref "C2") (pin "2") (pinfunction "2_2") (pintype "passive"))
      (node (ref "C20") (pin "2") (pinfunction "2_2") (pintype "passive"))
      (node (ref "C21") (pin "2") (pinfunction "2_2") (pintype "passive"))
      (node (ref "C25") (pin "2") (pinfunction "2_2") (pintype "passive"))
      (node (ref "C27") (pin "2") (pinfunction "2_2") (pintype "passive"))
      (node (ref "C28") (pin "2") (pinfunction "2_2") (pintype "passive"))
      (node (ref "C29") (pin "2") (pinfunction "2_2") (pintype "passive"))
      (node (ref "C3") (pin "-") (pinfunction "2(-)_-") (pintype "passive"))
      (node (ref "C30") (pin "2") (pinfunction "2_2") (pintype "passive"))
      (node (ref "C31") (pin "2") (pinfunction "2_2") (pintype "passive"))
      (node (ref "C32") (pin "2") (pinfunction "2_2") (pintype "passive"))
      (node (ref "C33") (pin "2") (pinfunction "2_2") (pintype "passive"))
      (node (ref "C34") (pin "2") (pinfunction "2_2") (pintype "passive"))
      (node (ref "C36") (pin "2") (pinfunction "2_2") (pintype "passive"))
      (node (ref "C37") (pin "2") (pinfunction "2_2") (pintype "passive"))
      (node (ref "C38") (pin "2") (pinfunction "2_2") (pintype "passive"))
      (node (ref "C4") (pin "2") (pinfunction "2_2") (pintype "passive"))
      (node (ref "C5") (pin "2") (pinfunction "2_2") (pintype "passive"))
      (node (ref "C6") (pin "-") (pinfunction "2(-)_-") (pintype "passive"))
      (node (ref "C7") (pin "2") (pinfunction "2_2") (pintype "passive"))
      (node (ref "C8") (pin "2") (pinfunction "2_2") (pintype "passive"))
      (node (ref "C9") (pin "-") (pinfunction "2(-)_-") (pintype "passive"))
      (node (ref "CR2") (pin "2") (pinfunction "P$1_2") (pintype "bidirectional"))
      (node (ref "D1") (pin "C") (pinfunction "C_C") (pintype "passive"))
      (node (ref "J1") (pin "4") (pinfunction "GND_4") (pintype "bidirectional"))
      (node (ref "J4") (pin "BLK") (pinfunction "GND_BLK") (pintype "power_in"))
      (node (ref "R29") (pin "1") (pinfunction "1_1") (pintype "passive"))
      (node (ref "R56") (pin "1") (pinfunction "1_1") (pintype "passive"))
      (node (ref "R57") (pin "1") (pinfunction "1_1") (pintype "passive"))
      (node (ref "R58") (pin "1") (pinfunction "1_1") (pintype "passive"))
      (node (ref "R59") (pin "1") (pinfunction "1_1") (pintype "passive"))
      (node (ref "R60") (pin "1") (pinfunction "1_1") (pintype "passive"))
      (node (ref "R61") (pin "1") (pinfunction "1_1") (pintype "passive"))
      (node (ref "R62") (pin "2") (pinfunction "2_2") (pintype "passive"))
      (node (ref "U1") (pin "4") (pinfunction "GND_4") (pintype "power_in"))
      (node (ref "U10") (pin "2") (pinfunction "GND1_2") (pintype "bidirectional"))
      (node (ref "U10") (pin "7") (pinfunction "GND1_7") (pintype "bidirectional"))
      (node (ref "U10") (pin "8") (pinfunction "GND1_8") (pintype "bidirectional"))
      (node (ref "U11") (pin "2") (pinfunction "GND_2") (pintype "power_in"))
      (node (ref "U11") (pin "21") (pinfunction "GND_21") (pintype "power_in"))
      (node (ref "U12") (pin "1") (pinfunction "GND_1") (pintype "power_in"))
      (node (ref "U14") (pin "14") (pinfunction "GND_14") (pintype "power_in"))
      (node (ref "U14") (pin "25") (pinfunction "EXTCLK_25") (pintype "input"))
      (node (ref "U2") (pin "4") (pinfunction "GND_4") (pintype "power_in"))
      (node (ref "U3") (pin "4") (pinfunction "GND_4") (pintype "power_in"))
      (node (ref "U4") (pin "4") (pinfunction "GND_4") (pintype "power_in"))
      (node (ref "U5") (pin "4") (pinfunction "GND_4") (pintype "power_in"))
      (node (ref "U6") (pin "4") (pinfunction "GND_4") (pintype "power_in"))
      (node (ref "U7") (pin "1") (pinfunction "~{LDAC}_1") (pintype "bidirectional"))
      (node (ref "U7") (pin "14") (pinfunction "GND_14") (pintype "bidirectional"))
      (node (ref "U8") (pin "5") (pinfunction "GND2_5") (pintype "power_in"))
      (node (ref "U9") (pin "28") (pinfunction "VSS_28") (pintype "power_in"))
    )
    (net (code "39") (name "I2C_3V3") (class "Default")
      (node (ref "C24") (pin "1") (pinfunction "1_1") (pintype "passive"))
      (node (ref "J2") (pin "5") (pinfunction "5_5") (pintype "bidirectional"))
      (node (ref "J3") (pin "5") (pinfunction "5_5") (pintype "bidirectional"))
      (node (ref "J6") (pin "5") (pinfunction "5_5") (pintype "bidirectional"))
      (node (ref "J7") (pin "3V3") (pinfunction "3V3_3V3") (pintype "bidirectional"))
      (node (ref "R12") (pin "2") (pinfunction "2_2") (pintype "passive"))
      (node (ref "R13") (pin "2") (pinfunction "2_2") (pintype "passive"))
      (node (ref "U8") (pin "1") (pinfunction "VCC1_1") (pintype "power_in"))
    )
    (net (code "40") (name "I2C_GND") (class "Default")
      (node (ref "C24") (pin "2") (pinfunction "2_2") (pintype "passive"))
      (node (ref "J2") (pin "1") (pinfunction "1_1") (pintype "bidirectional"))
      (node (ref "J3") (pin "1") (pinfunction "1_1") (pintype "bidirectional"))
      (node (ref "J6") (pin "1") (pinfunction "1_1") (pintype "bidirectional"))
      (node (ref "J7") (pin "GND") (pinfunction "GND_GND") (pintype "bidirectional"))
      (node (ref "U8") (pin "4") (pinfunction "GND1_4") (pintype "power_in"))
    )
    (net (code "41") (name "I2C_IO") (class "Default")
      (node (ref "J2") (pin "2") (pinfunction "2_2") (pintype "bidirectional"))
      (node (ref "J3") (pin "2") (pinfunction "2_2") (pintype "bidirectional"))
      (node (ref "J6") (pin "2") (pinfunction "2_2") (pintype "bidirectional"))
    )
    (net (code "42") (name "I2C_SCL") (class "Default")
      (node (ref "J2") (pin "3") (pinfunction "3_3") (pintype "bidirectional"))
      (node (ref "J3") (pin "3") (pinfunction "3_3") (pintype "bidirectional"))
      (node (ref "J6") (pin "3") (pinfunction "3_3") (pintype "bidirectional"))
      (node (ref "J7") (pin "SCL") (pinfunction "SCL_SCL") (pintype "bidirectional"))
      (node (ref "R12") (pin "1") (pinfunction "1_1") (pintype "passive"))
      (node (ref "U8") (pin "3") (pinfunction "SCL1_3") (pintype "bidirectional"))
    )
    (net (code "43") (name "I2C_SDA") (class "Default")
      (node (ref "J2") (pin "4") (pinfunction "4_4") (pintype "bidirectional"))
      (node (ref "J3") (pin "4") (pinfunction "4_4") (pintype "bidirectional"))
      (node (ref "J6") (pin "4") (pinfunction "4_4") (pintype "bidirectional"))
      (node (ref "J7") (pin "SDA") (pinfunction "SDA_SDA") (pintype "bidirectional"))
      (node (ref "R13") (pin "1") (pinfunction "1_1") (pintype "passive"))
      (node (ref "U8") (pin "2") (pinfunction "SDA1_2") (pintype "bidirectional"))
    )
    (net (code "44") (name "Net-(D1-PadA)") (class "Default")
      (node (ref "D1") (pin "A") (pinfunction "A_A") (pintype "passive"))
      (node (ref "R27") (pin "1") (pinfunction "1_1") (pintype "passive"))
    )
    (net (code "45") (name "Net-(U1-+VIN)") (class "Default")
      (node (ref "C1") (pin "1") (pinfunction "1_1") (pintype "passive"))
      (node (ref "L1") (pin "2") (pinfunction "2_2") (pintype "passive"))
      (node (ref "U1") (pin "1") (pinfunction "+VIN_1") (pintype "power_in"))
    )
    (net (code "46") (name "Net-(U2-+VIN)") (class "Default")
      (node (ref "C4") (pin "1") (pinfunction "1_1") (pintype "passive"))
      (node (ref "L2") (pin "2") (pinfunction "2_2") (pintype "passive"))
      (node (ref "U2") (pin "1") (pinfunction "+VIN_1") (pintype "power_in"))
    )
    (net (code "47") (name "Net-(U3-+VIN)") (class "Default")
      (node (ref "C7") (pin "1") (pinfunction "1_1") (pintype "passive"))
      (node (ref "L3") (pin "2") (pinfunction "2_2") (pintype "passive"))
      (node (ref "U3") (pin "1") (pinfunction "+VIN_1") (pintype "power_in"))
    )
    (net (code "48") (name "Net-(U4-+VIN)") (class "Default")
      (node (ref "C10") (pin "1") (pinfunction "1_1") (pintype "passive"))
      (node (ref "L4") (pin "2") (pinfunction "2_2") (pintype "passive"))
      (node (ref "U4") (pin "1") (pinfunction "+VIN_1") (pintype "power_in"))
    )
    (net (code "49") (name "Net-(U5-+VIN)") (class "Default")
      (node (ref "C13") (pin "1") (pinfunction "1_1") (pintype "passive"))
      (node (ref "L5") (pin "2") (pinfunction "2_2") (pintype "passive"))
      (node (ref "U5") (pin "1") (pinfunction "+VIN_1") (pintype "power_in"))
    )
    (net (code "50") (name "Net-(U6-+VIN)") (class "Default")
      (node (ref "C16") (pin "1") (pinfunction "1_1") (pintype "passive"))
      (node (ref "L6") (pin "2") (pinfunction "2_2") (pintype "passive"))
      (node (ref "U6") (pin "1") (pinfunction "+VIN_1") (pintype "power_in"))
    )
    (net (code "51") (name "Net-(U9-VCCD)") (class "Default")
      (node (ref "C33") (pin "1") (pinfunction "1_1") (pintype "passive"))
      (node (ref "U9") (pin "26") (pinfunction "VCCD_26") (pintype "power_in"))
    )
    (net (code "52") (name "Net-(U11-3V3)") (class "Default")
      (node (ref "C30") (pin "1") (pinfunction "1_1") (pintype "passive"))
      (node (ref "C34") (pin "1") (pinfunction "1_1") (pintype "passive"))
      (node (ref "R17") (pin "1") (pinfunction "1_1") (pintype "passive"))
      (node (ref "U11") (pin "24") (pinfunction "3V3_24") (pintype "power_in"))
    )
    (net (code "53") (name "P0[7]") (class "Default")
      (node (ref "R25") (pin "1") (pinfunction "1_1") (pintype "passive"))
      (node (ref "U9") (pin "24") (pinfunction "P0[7]_24") (pintype "bidirectional"))
    )
    (net (code "54") (name "P2[6]") (class "Default")
      (node (ref "R20") (pin "1") (pinfunction "1_1") (pintype "passive"))
      (node (ref "U9") (pin "9") (pinfunction "P2[6]_9") (pintype "bidirectional"))
    )
    (net (code "55") (name "P2[7]") (class "Default")
      (node (ref "R21") (pin "1") (pinfunction "1_1") (pintype "passive"))
      (node (ref "U9") (pin "10") (pinfunction "P2[7]_10") (pintype "bidirectional"))
    )
    (net (code "56") (name "PHOTON_A0") (class "Default")
      (node (ref "R24") (pin "1") (pinfunction "1_1") (pintype "passive"))
      (node (ref "U11") (pin "12") (pinfunction "A0_12") (pintype "bidirectional"))
    )
    (net (code "57") (name "PHOTON_D2") (class "Default")
      (node (ref "R23") (pin "1") (pinfunction "1_1") (pintype "passive"))
      (node (ref "U11") (pin "15") (pinfunction "D2_15") (pintype "bidirectional"))
    )
    (net (code "58") (name "PHOTON_D3") (class "Default")
      (node (ref "R22") (pin "1") (pinfunction "1_1") (pintype "passive"))
      (node (ref "U11") (pin "16") (pinfunction "D3_16") (pintype "bidirectional"))
    )
    (net (code "59") (name "PHOTON_D4") (class "Default")
      (node (ref "U11") (pin "17") (pinfunction "D4_17") (pintype "bidirectional"))
    )
    (net (code "60") (name "PHOTON_RX") (class "Default")
      (node (ref "R18") (pin "1") (pinfunction "1_1") (pintype "passive"))
      (node (ref "U11") (pin "4") (pinfunction "RX_4") (pintype "bidirectional"))
    )
    (net (code "61") (name "PHOTON_SCL") (class "Default")
      (node (ref "R5") (pin "1") (pinfunction "1_1") (pintype "passive"))
      (node (ref "U11") (pin "14") (pinfunction "D1_14") (pintype "bidirectional"))
    )
    (net (code "62") (name "PHOTON_SDA") (class "Default")
      (node (ref "R4") (pin "1") (pinfunction "1_1") (pintype "passive"))
      (node (ref "U11") (pin "13") (pinfunction "D0_13") (pintype "bidirectional"))
    )
    (net (code "63") (name "PHOTON_TX") (class "Default")
      (node (ref "R19") (pin "1") (pinfunction "1_1") (pintype "passive"))
      (node (ref "U11") (pin "3") (pinfunction "TX_3") (pintype "bidirectional"))
    )
    (net (code "64") (name "PWM1") (class "Default")
      (node (ref "U1") (pin "3") (pinfunction "PWM/ON/OFF_3") (pintype "bidirectional"))
      (node (ref "U14") (pin "7") (pinfunction "PWM1_7") (pintype "output"))
    )
    (net (code "65") (name "PWM2") (class "Default")
      (node (ref "U14") (pin "8") (pinfunction "PWM2_8") (pintype "output"))
      (node (ref "U2") (pin "3") (pinfunction "PWM/ON/OFF_3") (pintype "bidirectional"))
    )
    (net (code "66") (name "PWM3") (class "Default")
      (node (ref "U14") (pin "9") (pinfunction "PWM3_9") (pintype "output"))
      (node (ref "U3") (pin "3") (pinfunction "PWM/ON/OFF_3") (pintype "bidirectional"))
    )
    (net (code "67") (name "PWM4") (class "Default")
      (node (ref "U14") (pin "10") (pinfunction "PWM4_10") (pintype "output"))
      (node (ref "U4") (pin "3") (pinfunction "PWM/ON/OFF_3") (pintype "bidirectional"))
    )
    (net (code "68") (name "PWM5") (class "Default")
      (node (ref "U14") (pin "11") (pinfunction "PWM5_11") (pintype "output"))
      (node (ref "U5") (pin "3") (pinfunction "PWM/ON/OFF_3") (pintype "bidirectional"))
    )
    (net (code "69") (name "PWM6") (class "Default")
      (node (ref "U14") (pin "12") (pinfunction "PWM6_12") (pintype "output"))
      (node (ref "U6") (pin "3") (pinfunction "PWM/ON/OFF_3") (pintype "bidirectional"))
    )
    (net (code "70") (name "REG_3V3") (class "Default")
      (node (ref "C20") (pin "1") (pinfunction "1_1") (pintype "passive"))
      (node (ref "U12") (pin "3") (pinfunction "OUT_3") (pintype "output"))
    )
    (net (code "71") (name "SCB0_I2C_SCL") (class "Default")
      (node (ref "R2") (pin "1") (pinfunction "1_1") (pintype "passive"))
      (node (ref "U9") (pin "15") (pinfunction "P4[0]_15") (pintype "bidirectional"))
    )
    (net (code "72") (name "SCB0_I2C_SDA") (class "Default")
      (node (ref "R1") (pin "1") (pinfunction "1_1") (pintype "passive"))
      (node (ref "U9") (pin "16") (pinfunction "P4[1]_16") (pintype "bidirectional"))
    )
    (net (code "73") (name "SCB1_RX[0]") (class "Default")
      (node (ref "R15") (pin "1") (pinfunction "1_1") (pintype "passive"))
      (node (ref "U9") (pin "11") (pinfunction "P3[0]_11") (pintype "bidirectional"))
    )
    (net (code "74") (name "SCB1_TX[0]") (class "Default")
      (node (ref "R16") (pin "1") (pinfunction "1_1") (pintype "passive"))
      (node (ref "U9") (pin "12") (pinfunction "P3[1]_12") (pintype "bidirectional"))
    )
    (net (code "75") (name "SCL") (class "Default")
      (node (ref "R10") (pin "1") (pinfunction "1_1") (pintype "passive"))
      (node (ref "R2") (pin "2") (pinfunction "2_2") (pintype "passive"))
      (node (ref "R5") (pin "2") (pinfunction "2_2") (pintype "passive"))
      (node (ref "U14") (pin "26") (pinfunction "SCL_26") (pintype "bidirectional"))
      (node (ref "U7") (pin "16") (pinfunction "SCL_16") (pintype "bidirectional"))
      (node (ref "U8") (pin "6") (pinfunction "SCL2_6") (pintype "bidirectional"))
    )
    (net (code "76") (name "SDA") (class "Default")
      (node (ref "R1") (pin "2") (pinfunction "2_2") (pintype "passive"))
      (node (ref "R11") (pin "1") (pinfunction "1_1") (pintype "passive"))
      (node (ref "R4") (pin "2") (pinfunction "2_2") (pintype "passive"))
      (node (ref "U14") (pin "27") (pinfunction "SDA_27") (pintype "bidirectional"))
      (node (ref "U7") (pin "15") (pinfunction "SDA_15") (pintype "bidirectional"))
      (node (ref "U8") (pin "7") (pinfunction "SDA2_7") (pintype "bidirectional"))
    )
    (net (code "77") (name "SWD_CLK[0]") (class "Default")
      (node (ref "J1") (pin "2") (pinfunction "SCLK_2") (pintype "bidirectional"))
      (node (ref "U9") (pin "14") (pinfunction "P3[3]_14") (pintype "bidirectional"))
    )
    (net (code "78") (name "SWD_IO[0]") (class "Default")
      (node (ref "J1") (pin "1") (pinfunction "SDAT_1") (pintype "bidirectional"))
      (node (ref "U9") (pin "13") (pinfunction "P3[2]_13") (pintype "bidirectional"))
    )
    (net (code "79") (name "UART_DE") (class "Default")
      (node (ref "R20") (pin "2") (pinfunction "2_2") (pintype "passive"))
      (node (ref "R22") (pin "2") (pinfunction "2_2") (pintype "passive"))
      (node (ref "U10") (pin "5") (pinfunction "DE_5") (pintype "bidirectional"))
    )
    (net (code "80") (name "UART_RX") (class "Default")
      (node (ref "R15") (pin "2") (pinfunction "2_2") (pintype "passive"))
      (node (ref "R18") (pin "2") (pinfunction "2_2") (pintype "passive"))
      (node (ref "U10") (pin "3") (pinfunction "RXD_3") (pintype "bidirectional"))
    )
    (net (code "81") (name "UART_TX") (class "Default")
      (node (ref "R16") (pin "2") (pinfunction "2_2") (pintype "passive"))
      (node (ref "R19") (pin "2") (pinfunction "2_2") (pintype "passive"))
      (node (ref "U10") (pin "6") (pinfunction "TXD_6") (pintype "bidirectional"))
    )
    (net (code "82") (name "VCC") (class "Default")
      (node (ref "C21") (pin "1") (pinfunction "1_1") (pintype "passive"))
      (node (ref "SJ_A0") (pin "1") (pinfunction "1_1") (pintype "passive"))
      (node (ref "SJ_A1") (pin "1") (pinfunction "1_1") (pintype "passive"))
      (node (ref "SJ_A2") (pin "1") (pinfunction "1_1") (pintype "passive"))
      (node (ref "SJ_A3") (pin "1") (pinfunction "1_1") (pintype "passive"))
      (node (ref "SJ_A4") (pin "1") (pinfunction "1_1") (pintype "passive"))
      (node (ref "SJ_A5") (pin "1") (pinfunction "1_1") (pintype "passive"))
      (node (ref "U14") (pin "28") (pinfunction "VDD_28") (pintype "power_in"))
    )
    (net (code "83") (name "VDDD") (class "Default")
      (node (ref "C31") (pin "1") (pinfunction "1_1") (pintype "passive"))
      (node (ref "C32") (pin "1") (pinfunction "1_1") (pintype "passive"))
      (node (ref "J1") (pin "5") (pinfunction "VTARG_5") (pintype "bidirectional"))
      (node (ref "R3") (pin "2") (pinfunction "2_2") (pintype "passive"))
      (node (ref "U9") (pin "27") (pinfunction "VDDD_27") (pintype "power_in"))
    )
    (net (code "84") (name "XRES") (class "Default")
      (node (ref "J1") (pin "3") (pinfunction "XRES_3") (pintype "bidirectional"))
      (node (ref "U9") (pin "25") (pinfunction "XRES_25") (pintype "input"))
    )
    (net (code "85") (name "unconnected-(J2-Pad6)") (class "Default")
      (node (ref "J2") (pin "6") (pinfunction "6_6") (pintype "bidirectional"))
    )
    (net (code "86") (name "unconnected-(J3-Pad6)") (class "Default")
      (node (ref "J3") (pin "6") (pinfunction "6_6") (pintype "bidirectional"))
    )
    (net (code "87") (name "unconnected-(J5-Pad5)") (class "Default")
      (node (ref "J5") (pin "5") (pinfunction "5_5") (pintype "bidirectional"))
    )
    (net (code "88") (name "unconnected-(J6-Pad6)") (class "Default")
      (node (ref "J6") (pin "6") (pinfunction "6_6") (pintype "bidirectional"))
    )
    (net (code "89") (name "unconnected-(SW1-P1-Pad4)") (class "Default")
      (node (ref "SW1") (pin "4") (pinfunction "P1_4") (pintype "passive"))
    )
    (net (code "90") (name "unconnected-(SW1-S1-Pad2)") (class "Default")
      (node (ref "SW1") (pin "2") (pinfunction "S1_2") (pintype "passive"))
    )
    (net (code "91") (name "unconnected-(U7-ADDR0-Pad2)") (class "Default")
      (node (ref "U7") (pin "2") (pinfunction "ADDR0_2") (pintype "bidirectional"))
    )
    (net (code "92") (name "unconnected-(U7-VOUT_B-Pad13)") (class "Default")
      (node (ref "U7") (pin "13") (pinfunction "VOUT_B_13") (pintype "bidirectional"))
    )
    (net (code "93") (name "unconnected-(U7-VOUT_D-Pad12)") (class "Default")
      (node (ref "U7") (pin "12") (pinfunction "VOUT_D_12") (pintype "bidirectional"))
    )
    (net (code "94") (name "unconnected-(U9-P0[0]-Pad19)") (class "Default")
      (node (ref "U9") (pin "19") (pinfunction "P0[0]_19") (pintype "bidirectional"))
    )
    (net (code "95") (name "unconnected-(U9-P0[1]-Pad20)") (class "Default")
      (node (ref "U9") (pin "20") (pinfunction "P0[1]_20") (pintype "bidirectional"))
    )
    (net (code "96") (name "unconnected-(U9-P0[2]-Pad21)") (class "Default")
      (node (ref "U9") (pin "21") (pinfunction "P0[2]_21") (pintype "bidirectional"))
    )
    (net (code "97") (name "unconnected-(U9-P0[3]-Pad22)") (class "Default")
      (node (ref "U9") (pin "22") (pinfunction "P0[3]_22") (pintype "bidirectional"))
    )
    (net (code "98") (name "unconnected-(U9-P0[6]-Pad23)") (class "Default")
      (node (ref "U9") (pin "23") (pinfunction "P0[6]_23") (pintype "bidirectional"))
    )
    (net (code "99") (name "unconnected-(U9-P1[0]-Pad1)") (class "Default")
      (node (ref "U9") (pin "1") (pinfunction "P1[0]_1") (pintype "bidirectional"))
    )
    (net (code "100") (name "unconnected-(U9-P1[1]-Pad2)") (class "Default")
      (node (ref "U9") (pin "2") (pinfunction "P1[1]_2") (pintype "bidirectional"))
    )
    (net (code "101") (name "unconnected-(U9-P1[2]-Pad3)") (class "Default")
      (node (ref "U9") (pin "3") (pinfunction "P1[2]_3") (pintype "bidirectional"))
    )
    (net (code "102") (name "unconnected-(U9-P1[7]-Pad4)") (class "Default")
      (node (ref "U9") (pin "4") (pinfunction "P1[7]_4") (pintype "bidirectional"))
    )
    (net (code "103") (name "unconnected-(U9-P2[2]-Pad5)") (class "Default")
      (node (ref "U9") (pin "5") (pinfunction "P2[2]_5") (pintype "bidirectional"))
    )
    (net (code "104") (name "unconnected-(U9-P2[3]-Pad6)") (class "Default")
      (node (ref "U9") (pin "6") (pinfunction "P2[3]_6") (pintype "bidirectional"))
    )
    (net (code "105") (name "unconnected-(U9-P2[4]-Pad7)") (class "Default")
      (node (ref "U9") (pin "7") (pinfunction "P2[4]_7") (pintype "bidirectional"))
    )
    (net (code "106") (name "unconnected-(U9-P2[5]-Pad8)") (class "Default")
      (node (ref "U9") (pin "8") (pinfunction "P2[5]_8") (pintype "bidirectional"))
    )
    (net (code "107") (name "unconnected-(U9-P4[2]-Pad17)") (class "Default")
      (node (ref "U9") (pin "17") (pinfunction "P4[2]_17") (pintype "bidirectional"))
    )
    (net (code "108") (name "unconnected-(U9-P4[3]-Pad18)") (class "Default")
      (node (ref "U9") (pin "18") (pinfunction "P4[3]_18") (pintype "bidirectional"))
    )
    (net (code "109") (name "unconnected-(U11-A1-Pad11)") (class "Default")
      (node (ref "U11") (pin "11") (pinfunction "A1_11") (pintype "bidirectional"))
    )
    (net (code "110") (name "unconnected-(U11-A2-Pad10)") (class "Default")
      (node (ref "U11") (pin "10") (pinfunction "A2_10") (pintype "bidirectional"))
    )
    (net (code "111") (name "unconnected-(U11-A3-Pad9)") (class "Default")
      (node (ref "U11") (pin "9") (pinfunction "A3_9") (pintype "bidirectional"))
    )
    (net (code "112") (name "unconnected-(U11-A4-Pad8)") (class "Default")
      (node (ref "U11") (pin "8") (pinfunction "A4_8") (pintype "bidirectional"))
    )
    (net (code "113") (name "unconnected-(U11-A5-Pad7)") (class "Default")
      (node (ref "U11") (pin "7") (pinfunction "A5_7") (pintype "bidirectional"))
    )
    (net (code "114") (name "unconnected-(U11-D5-Pad18)") (class "Default")
      (node (ref "U11") (pin "18") (pinfunction "D5_18") (pintype "bidirectional"))
    )
    (net (code "115") (name "unconnected-(U11-D6-Pad19)") (class "Default")
      (node (ref "U11") (pin "19") (pinfunction "D6_19") (pintype "bidirectional"))
    )
    (net (code "116") (name "unconnected-(U11-D7-Pad20)") (class "Default")
      (node (ref "U11") (pin "20") (pinfunction "D7_20") (pintype "bidirectional"))
    )
    (net (code "117") (name "unconnected-(U11-DAC-Pad6)") (class "Default")
      (node (ref "U11") (pin "6") (pinfunction "DAC_6") (pintype "bidirectional"))
    )
    (net (code "118") (name "unconnected-(U11-WKP-Pad5)") (class "Default")
      (node (ref "U11") (pin "5") (pinfunction "WKP_5") (pintype "bidirectional"))
    )
    (net (code "119") (name "unconnected-(U11-~{RST}-Pad23)") (class "Default")
      (node (ref "U11") (pin "23") (pinfunction "~{RST}_23") (pintype "bidirectional"))
    )
    (net (code "120") (name "unconnected-(U12-NC-Pad5)") (class "Default")
      (node (ref "U12") (pin "5") (pinfunction "NC_5") (pintype "passive"))
    )
    (net (code "121") (name "unconnected-(U12-NC_2-Pad4)") (class "Default")
      (node (ref "U12") (pin "4") (pinfunction "NC_2_4") (pintype "passive"))
    )
    (net (code "122") (name "unconnected-(U14-PWM0-Pad6)") (class "Default")
      (node (ref "U14") (pin "6") (pinfunction "PWM0_6") (pintype "output"))
    )
    (net (code "123") (name "unconnected-(U14-PWM7-Pad13)") (class "Default")
      (node (ref "U14") (pin "13") (pinfunction "PWM7_13") (pintype "output"))
    )
    (net (code "124") (name "unconnected-(U14-PWM8-Pad15)") (class "Default")
      (node (ref "U14") (pin "15") (pinfunction "PWM8_15") (pintype "output"))
    )
    (net (code "125") (name "unconnected-(U14-PWM9-Pad16)") (class "Default")
      (node (ref "U14") (pin "16") (pinfunction "PWM9_16") (pintype "output"))
    )
    (net (code "126") (name "unconnected-(U14-PWM10-Pad17)") (class "Default")
      (node (ref "U14") (pin "17") (pinfunction "PWM10_17") (pintype "output"))
    )
    (net (code "127") (name "unconnected-(U14-PWM11-Pad18)") (class "Default")
      (node (ref "U14") (pin "18") (pinfunction "PWM11_18") (pintype "output"))
    )
    (net (code "128") (name "unconnected-(U14-PWM12-Pad19)") (class "Default")
      (node (ref "U14") (pin "19") (pinfunction "PWM12_19") (pintype "output"))
    )
    (net (code "129") (name "unconnected-(U14-PWM13-Pad20)") (class "Default")
      (node (ref "U14") (pin "20") (pinfunction "PWM13_20") (pintype "output"))
    )
    (net (code "130") (name "unconnected-(U14-PWM14-Pad21)") (class "Default")
      (node (ref "U14") (pin "21") (pinfunction "PWM14_21") (pintype "output"))
    )
    (net (code "131") (name "unconnected-(U14-PWM15-Pad22)") (class "Default")
      (node (ref "U14") (pin "22") (pinfunction "PWM15_22") (pintype "output"))
    )
  )
)
